# CF_FMC_DE.net
KiCad netlist of a schematic drawn in Altium Designer
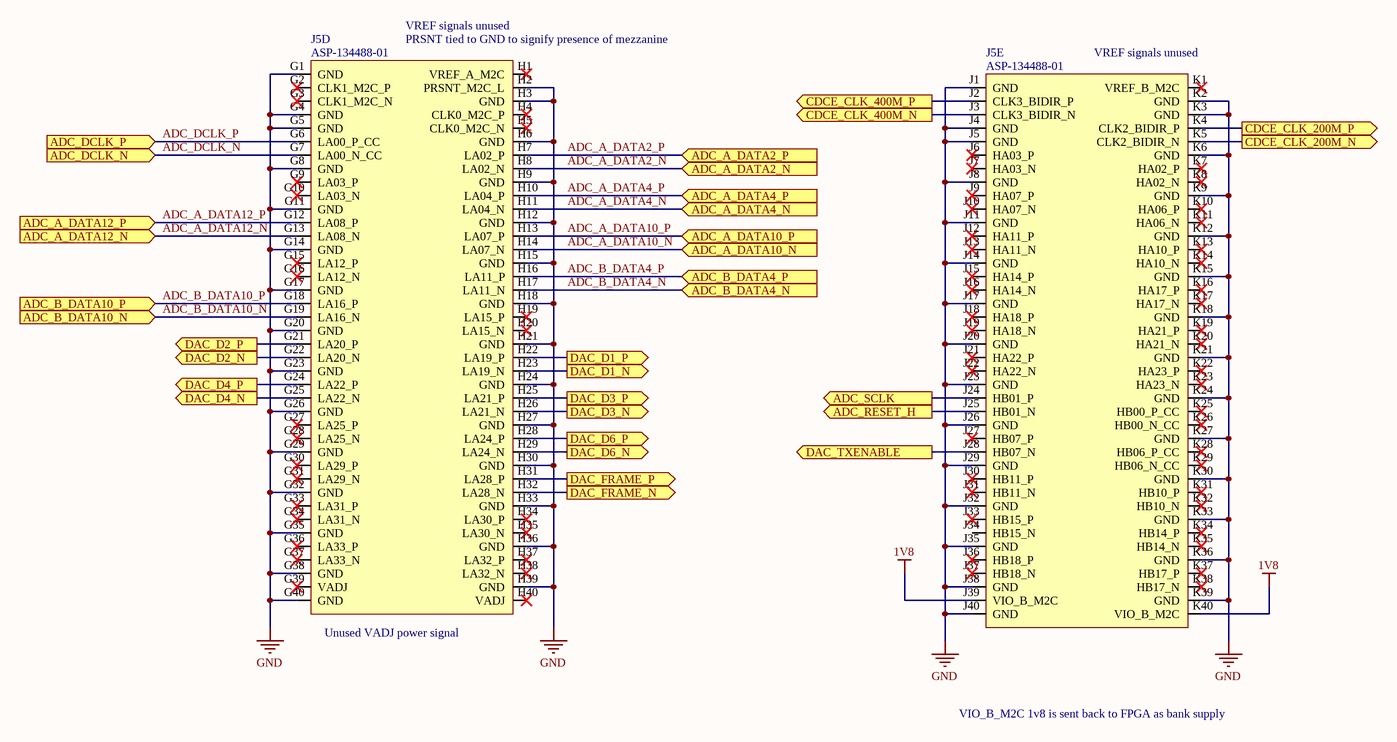
[diagram p0: CF_FMC_DE.SchDoc]

(export (version "E")
  (design (tool "Eeschema 10.0.6"))
  (components
    (comp (ref "J5")
      (value "ASP-134488-01")
      (footprint "CONN_SAMTEC_ASP-134488-01")
      (description "CONN - VITA 57 MEZZ MALE (DAUGHTERBOARD) HIGH DENSITY - SMD-400")
      (fields
        (field (name "VOLTAGE") "240VAC")
        (field (name "MFG") "Samtec")
        (field (name "CREATEDBY") "Jonathan Bouchard")
      )
      (libsource (lib "S7CAS_Lib2019_REV1_00") (part "CONN_SAMTEC_ASP-134488-01"))
    )
  )
  (nets
    (net (code "1") (name "/ADC_A_DATA2_N") (class "Default")
      (node (ref "J5") (pin "H8") (pinfunction "LA02_N_H8") (pintype "passive"))
    )
    (net (code "2") (name "/ADC_A_DATA2_P") (class "Default")
      (node (ref "J5") (pin "H7") (pinfunction "LA02_P_H7") (pintype "passive"))
    )
    (net (code "3") (name "/ADC_A_DATA4_N") (class "Default")
      (node (ref "J5") (pin "H11") (pinfunction "LA04_N_H11") (pintype "passive"))
    )
    (net (code "4") (name "/ADC_A_DATA4_P") (class "Default")
      (node (ref "J5") (pin "H10") (pinfunction "LA04_P_H10") (pintype "passive"))
    )
    (net (code "5") (name "/ADC_A_DATA10_N") (class "Default")
      (node (ref "J5") (pin "H14") (pinfunction "LA07_N_H14") (pintype "passive"))
    )
    (net (code "6") (name "/ADC_A_DATA10_P") (class "Default")
      (node (ref "J5") (pin "H13") (pinfunction "LA07_P_H13") (pintype "passive"))
    )
    (net (code "7") (name "/ADC_A_DATA12_N") (class "Default")
      (node (ref "J5") (pin "G13") (pinfunction "LA08_N_G13") (pintype "passive"))
    )
    (net (code "8") (name "/ADC_A_DATA12_P") (class "Default")
      (node (ref "J5") (pin "G12") (pinfunction "LA08_P_G12") (pintype "passive"))
    )
    (net (code "9") (name "/ADC_B_DATA4_N") (class "Default")
      (node (ref "J5") (pin "H17") (pinfunction "LA11_N_H17") (pintype "passive"))
    )
    (net (code "10") (name "/ADC_B_DATA4_P") (class "Default")
      (node (ref "J5") (pin "H16") (pinfunction "LA11_P_H16") (pintype "passive"))
    )
    (net (code "11") (name "/ADC_B_DATA10_N") (class "Default")
      (node (ref "J5") (pin "G19") (pinfunction "LA16_N_G19") (pintype "passive"))
    )
    (net (code "12") (name "/ADC_B_DATA10_P") (class "Default")
      (node (ref "J5") (pin "G18") (pinfunction "LA16_P_G18") (pintype "passive"))
    )
    (net (code "13") (name "/ADC_DCLK_N") (class "Default")
      (node (ref "J5") (pin "G7") (pinfunction "LA00_N_CC_G7") (pintype "passive"))
    )
    (net (code "14") (name "/ADC_DCLK_P") (class "Default")
      (node (ref "J5") (pin "G6") (pinfunction "LA00_P_CC_G6") (pintype "passive"))
    )
    (net (code "15") (name "/ADC_RESET_H") (class "Default")
      (node (ref "J5") (pin "J25") (pinfunction "HB01_N_J25") (pintype "passive"))
    )
    (net (code "16") (name "/ADC_SCLK") (class "Default")
      (node (ref "J5") (pin "J24") (pinfunction "HB01_P_J24") (pintype "passive"))
    )
    (net (code "17") (name "/CDCE_CLK_200M_N") (class "Default")
      (node (ref "J5") (pin "K5") (pinfunction "CLK2_BIDIR_N_K5") (pintype "passive"))
    )
    (net (code "18") (name "/CDCE_CLK_200M_P") (class "Default")
      (node (ref "J5") (pin "K4") (pinfunction "CLK2_BIDIR_P_K4") (pintype "passive"))
    )
    (net (code "19") (name "/CDCE_CLK_400M_N") (class "Default")
      (node (ref "J5") (pin "J3") (pinfunction "CLK3_BIDIR_N_J3") (pintype "passive"))
    )
    (net (code "20") (name "/CDCE_CLK_400M_P") (class "Default")
      (node (ref "J5") (pin "J2") (pinfunction "CLK3_BIDIR_P_J2") (pintype "passive"))
    )
    (net (code "21") (name "/DAC_D1_N") (class "Default")
      (node (ref "J5") (pin "H23") (pinfunction "LA19_N_H23") (pintype "passive"))
    )
    (net (code "22") (name "/DAC_D1_P") (class "Default")
      (node (ref "J5") (pin "H22") (pinfunction "LA19_P_H22") (pintype "passive"))
    )
    (net (code "23") (name "/DAC_D2_N") (class "Default")
      (node (ref "J5") (pin "G22") (pinfunction "LA20_N_G22") (pintype "passive"))
    )
    (net (code "24") (name "/DAC_D2_P") (class "Default")
      (node (ref "J5") (pin "G21") (pinfunction "LA20_P_G21") (pintype "passive"))
    )
    (net (code "25") (name "/DAC_D3_N") (class "Default")
      (node (ref "J5") (pin "H26") (pinfunction "LA21_N_H26") (pintype "passive"))
    )
    (net (code "26") (name "/DAC_D3_P") (class "Default")
      (node (ref "J5") (pin "H25") (pinfunction "LA21_P_H25") (pintype "passive"))
    )
    (net (code "27") (name "/DAC_D4_N") (class "Default")
      (node (ref "J5") (pin "G25") (pinfunction "LA22_N_G25") (pintype "passive"))
    )
    (net (code "28") (name "/DAC_D4_P") (class "Default")
      (node (ref "J5") (pin "G24") (pinfunction "LA22_P_G24") (pintype "passive"))
    )
    (net (code "29") (name "/DAC_D6_N") (class "Default")
      (node (ref "J5") (pin "H29") (pinfunction "LA24_N_H29") (pintype "passive"))
    )
    (net (code "30") (name "/DAC_D6_P") (class "Default")
      (node (ref "J5") (pin "H28") (pinfunction "LA24_P_H28") (pintype "passive"))
    )
    (net (code "31") (name "/DAC_FRAME_N") (class "Default")
      (node (ref "J5") (pin "H32") (pinfunction "LA28_N_H32") (pintype "passive"))
    )
    (net (code "32") (name "/DAC_FRAME_P") (class "Default")
      (node (ref "J5") (pin "H31") (pinfunction "LA28_P_H31") (pintype "passive"))
    )
    (net (code "33") (name "/DAC_TXENABLE") (class "Default")
      (node (ref "J5") (pin "J28") (pinfunction "HB07_N_J28") (pintype "passive"))
    )
    (net (code "34") (name "1V8") (class "Default")
      (node (ref "J5") (pin "J39") (pinfunction "VIO_B_M2C_J39") (pintype "passive"))
      (node (ref "J5") (pin "K40") (pinfunction "VIO_B_M2C_K40") (pintype "passive"))
    )
    (net (code "35") (name "GND") (class "Default")
      (node (ref "J5") (pin "G1") (pinfunction "GND_G1") (pintype "passive"))
      (node (ref "J5") (pin "G11") (pinfunction "GND_G11") (pintype "passive"))
      (node (ref "J5") (pin "G14") (pinfunction "GND_G14") (pintype "passive"))
      (node (ref "J5") (pin "G17") (pinfunction "GND_G17") (pintype "passive"))
      (node (ref "J5") (pin "G20") (pinfunction "GND_G20") (pintype "passive"))
      (node (ref "J5") (pin "G23") (pinfunction "GND_G23") (pintype "passive"))
      (node (ref "J5") (pin "G26") (pinfunction "GND_G26") (pintype "passive"))
      (node (ref "J5") (pin "G29") (pinfunction "GND_G29") (pintype "passive"))
      (node (ref "J5") (pin "G32") (pinfunction "GND_G32") (pintype "passive"))
      (node (ref "J5") (pin "G35") (pinfunction "GND_G35") (pintype "passive"))
      (node (ref "J5") (pin "G38") (pinfunction "GND_G38") (pintype "passive"))
      (node (ref "J5") (pin "G4") (pinfunction "GND_G4") (pintype "passive"))
      (node (ref "J5") (pin "G40") (pinfunction "GND_G40") (pintype "passive"))
      (node (ref "J5") (pin "G5") (pinfunction "GND_G5") (pintype "passive"))
      (node (ref "J5") (pin "G8") (pinfunction "GND_G8") (pintype "passive"))
      (node (ref "J5") (pin "H12") (pinfunction "GND_H12") (pintype "passive"))
      (node (ref "J5") (pin "H15") (pinfunction "GND_H15") (pintype "passive"))
      (node (ref "J5") (pin "H18") (pinfunction "GND_H18") (pintype "passive"))
      (node (ref "J5") (pin "H2") (pinfunction "PRSNT_M2C_L_H2") (pintype "passive"))
      (node (ref "J5") (pin "H21") (pinfunction "GND_H21") (pintype "passive"))
      (node (ref "J5") (pin "H24") (pinfunction "GND_H24") (pintype "passive"))
      (node (ref "J5") (pin "H27") (pinfunction "GND_H27") (pintype "passive"))
      (node (ref "J5") (pin "H3") (pinfunction "GND_H3") (pintype "passive"))
      (node (ref "J5") (pin "H30") (pinfunction "GND_H30") (pintype "passive"))
      (node (ref "J5") (pin "H33") (pinfunction "GND_H33") (pintype "passive"))
      (node (ref "J5") (pin "H36") (pinfunction "GND_H36") (pintype "passive"))
      (node (ref "J5") (pin "H39") (pinfunction "GND_H39") (pintype "passive"))
      (node (ref "J5") (pin "H6") (pinfunction "GND_H6") (pintype "passive"))
      (node (ref "J5") (pin "H9") (pinfunction "GND_H9") (pintype "passive"))
      (node (ref "J5") (pin "J1") (pinfunction "GND_J1") (pintype "passive"))
      (node (ref "J5") (pin "J11") (pinfunction "GND_J11") (pintype "passive"))
      (node (ref "J5") (pin "J14") (pinfunction "GND_J14") (pintype "passive"))
      (node (ref "J5") (pin "J17") (pinfunction "GND_J17") (pintype "passive"))
      (node (ref "J5") (pin "J20") (pinfunction "GND_J20") (pintype "passive"))
      (node (ref "J5") (pin "J23") (pinfunction "GND_J23") (pintype "passive"))
      (node (ref "J5") (pin "J26") (pinfunction "GND_J26") (pintype "passive"))
      (node (ref "J5") (pin "J29") (pinfunction "GND_J29") (pintype "passive"))
      (node (ref "J5") (pin "J32") (pinfunction "GND_J32") (pintype "passive"))
      (node (ref "J5") (pin "J35") (pinfunction "GND_J35") (pintype "passive"))
      (node (ref "J5") (pin "J38") (pinfunction "GND_J38") (pintype "passive"))
      (node (ref "J5") (pin "J4") (pinfunction "GND_J4") (pintype "passive"))
      (node (ref "J5") (pin "J40") (pinfunction "GND_J40") (pintype "passive"))
      (node (ref "J5") (pin "J5") (pinfunction "GND_J5") (pintype "passive"))
      (node (ref "J5") (pin "J8") (pinfunction "GND_J8") (pintype "passive"))
      (node (ref "J5") (pin "K12") (pinfunction "GND_K12") (pintype "passive"))
      (node (ref "J5") (pin "K15") (pinfunction "GND_K15") (pintype "passive"))
      (node (ref "J5") (pin "K18") (pinfunction "GND_K18") (pintype "passive"))
      (node (ref "J5") (pin "K2") (pinfunction "GND_K2") (pintype "passive"))
      (node (ref "J5") (pin "K21") (pinfunction "GND_K21") (pintype "passive"))
      (node (ref "J5") (pin "K24") (pinfunction "GND_K24") (pintype "passive"))
      (node (ref "J5") (pin "K27") (pinfunction "GND_K27") (pintype "passive"))
      (node (ref "J5") (pin "K3") (pinfunction "GND_K3") (pintype "passive"))
      (node (ref "J5") (pin "K30") (pinfunction "GND_K30") (pintype "passive"))
      (node (ref "J5") (pin "K33") (pinfunction "GND_K33") (pintype "passive"))
      (node (ref "J5") (pin "K36") (pinfunction "GND_K36") (pintype "passive"))
      (node (ref "J5") (pin "K39") (pinfunction "GND_K39") (pintype "passive"))
      (node (ref "J5") (pin "K6") (pinfunction "GND_K6") (pintype "passive"))
      (node (ref "J5") (pin "K9") (pinfunction "GND_K9") (pintype "passive"))
    )
    (net (code "36") (name "unconnected-(J5D-CLK0_M2C_N-PadH5)") (class "Default")
      (node (ref "J5") (pin "H5") (pinfunction "CLK0_M2C_N_H5") (pintype "passive+no_connect"))
    )
    (net (code "37") (name "unconnected-(J5D-CLK0_M2C_P-PadH4)") (class "Default")
      (node (ref "J5") (pin "H4") (pinfunction "CLK0_M2C_P_H4") (pintype "passive+no_connect"))
    )
    (net (code "38") (name "unconnected-(J5D-CLK1_M2C_N-PadG3)") (class "Default")
      (node (ref "J5") (pin "G3") (pinfunction "CLK1_M2C_N_G3") (pintype "passive+no_connect"))
    )
    (net (code "39") (name "unconnected-(J5D-CLK1_M2C_P-PadG2)") (class "Default")
      (node (ref "J5") (pin "G2") (pinfunction "CLK1_M2C_P_G2") (pintype "passive+no_connect"))
    )
    (net (code "40") (name "unconnected-(J5D-LA03_N-PadG10)") (class "Default")
      (node (ref "J5") (pin "G10") (pinfunction "LA03_N_G10") (pintype "passive+no_connect"))
    )
    (net (code "41") (name "unconnected-(J5D-LA03_P-PadG9)") (class "Default")
      (node (ref "J5") (pin "G9") (pinfunction "LA03_P_G9") (pintype "passive+no_connect"))
    )
    (net (code "42") (name "unconnected-(J5D-LA12_N-PadG16)") (class "Default")
      (node (ref "J5") (pin "G16") (pinfunction "LA12_N_G16") (pintype "passive+no_connect"))
    )
    (net (code "43") (name "unconnected-(J5D-LA12_P-PadG15)") (class "Default")
      (node (ref "J5") (pin "G15") (pinfunction "LA12_P_G15") (pintype "passive+no_connect"))
    )
    (net (code "44") (name "unconnected-(J5D-LA15_N-PadH20)") (class "Default")
      (node (ref "J5") (pin "H20") (pinfunction "LA15_N_H20") (pintype "passive+no_connect"))
    )
    (net (code "45") (name "unconnected-(J5D-LA15_P-PadH19)") (class "Default")
      (node (ref "J5") (pin "H19") (pinfunction "LA15_P_H19") (pintype "passive+no_connect"))
    )
    (net (code "46") (name "unconnected-(J5D-LA25_N-PadG28)") (class "Default")
      (node (ref "J5") (pin "G28") (pinfunction "LA25_N_G28") (pintype "passive+no_connect"))
    )
    (net (code "47") (name "unconnected-(J5D-LA25_P-PadG27)") (class "Default")
      (node (ref "J5") (pin "G27") (pinfunction "LA25_P_G27") (pintype "passive+no_connect"))
    )
    (net (code "48") (name "unconnected-(J5D-LA29_N-PadG31)") (class "Default")
      (node (ref "J5") (pin "G31") (pinfunction "LA29_N_G31") (pintype "passive+no_connect"))
    )
    (net (code "49") (name "unconnected-(J5D-LA29_P-PadG30)") (class "Default")
      (node (ref "J5") (pin "G30") (pinfunction "LA29_P_G30") (pintype "passive+no_connect"))
    )
    (net (code "50") (name "unconnected-(J5D-LA30_N-PadH35)") (class "Default")
      (node (ref "J5") (pin "H35") (pinfunction "LA30_N_H35") (pintype "passive+no_connect"))
    )
    (net (code "51") (name "unconnected-(J5D-LA30_P-PadH34)") (class "Default")
      (node (ref "J5") (pin "H34") (pinfunction "LA30_P_H34") (pintype "passive+no_connect"))
    )
    (net (code "52") (name "unconnected-(J5D-LA31_N-PadG34)") (class "Default")
      (node (ref "J5") (pin "G34") (pinfunction "LA31_N_G34") (pintype "passive+no_connect"))
    )
    (net (code "53") (name "unconnected-(J5D-LA31_P-PadG33)") (class "Default")
      (node (ref "J5") (pin "G33") (pinfunction "LA31_P_G33") (pintype "passive+no_connect"))
    )
    (net (code "54") (name "unconnected-(J5D-LA32_N-PadH38)") (class "Default")
      (node (ref "J5") (pin "H38") (pinfunction "LA32_N_H38") (pintype "passive+no_connect"))
    )
    (net (code "55") (name "unconnected-(J5D-LA32_P-PadH37)") (class "Default")
      (node (ref "J5") (pin "H37") (pinfunction "LA32_P_H37") (pintype "passive+no_connect"))
    )
    (net (code "56") (name "unconnected-(J5D-LA33_N-PadG37)") (class "Default")
      (node (ref "J5") (pin "G37") (pinfunction "LA33_N_G37") (pintype "passive+no_connect"))
    )
    (net (code "57") (name "unconnected-(J5D-LA33_P-PadG36)") (class "Default")
      (node (ref "J5") (pin "G36") (pinfunction "LA33_P_G36") (pintype "passive+no_connect"))
    )
    (net (code "58") (name "unconnected-(J5D-VADJ-PadG39)") (class "Default")
      (node (ref "J5") (pin "G39") (pinfunction "VADJ_G39") (pintype "passive+no_connect"))
    )
    (net (code "59") (name "unconnected-(J5D-VADJ-PadH40)") (class "Default")
      (node (ref "J5") (pin "H40") (pinfunction "VADJ_H40") (pintype "passive+no_connect"))
    )
    (net (code "60") (name "unconnected-(J5D-VREF_A_M2C-PadH1)") (class "Default")
      (node (ref "J5") (pin "H1") (pinfunction "VREF_A_M2C_H1") (pintype "passive+no_connect"))
    )
    (net (code "61") (name "unconnected-(J5E-HA02_N-PadK8)") (class "Default")
      (node (ref "J5") (pin "K8") (pinfunction "HA02_N_K8") (pintype "passive+no_connect"))
    )
    (net (code "62") (name "unconnected-(J5E-HA02_P-PadK7)") (class "Default")
      (node (ref "J5") (pin "K7") (pinfunction "HA02_P_K7") (pintype "passive+no_connect"))
    )
    (net (code "63") (name "unconnected-(J5E-HA03_N-PadJ7)") (class "Default")
      (node (ref "J5") (pin "J7") (pinfunction "HA03_N_J7") (pintype "passive+no_connect"))
    )
    (net (code "64") (name "unconnected-(J5E-HA03_P-PadJ6)") (class "Default")
      (node (ref "J5") (pin "J6") (pinfunction "HA03_P_J6") (pintype "passive+no_connect"))
    )
    (net (code "65") (name "unconnected-(J5E-HA06_N-PadK11)") (class "Default")
      (node (ref "J5") (pin "K11") (pinfunction "HA06_N_K11") (pintype "passive+no_connect"))
    )
    (net (code "66") (name "unconnected-(J5E-HA06_P-PadK10)") (class "Default")
      (node (ref "J5") (pin "K10") (pinfunction "HA06_P_K10") (pintype "passive+no_connect"))
    )
    (net (code "67") (name "unconnected-(J5E-HA07_N-PadJ10)") (class "Default")
      (node (ref "J5") (pin "J10") (pinfunction "HA07_N_J10") (pintype "passive+no_connect"))
    )
    (net (code "68") (name "unconnected-(J5E-HA07_P-PadJ9)") (class "Default")
      (node (ref "J5") (pin "J9") (pinfunction "HA07_P_J9") (pintype "passive+no_connect"))
    )
    (net (code "69") (name "unconnected-(J5E-HA10_N-PadK14)") (class "Default")
      (node (ref "J5") (pin "K14") (pinfunction "HA10_N_K14") (pintype "passive+no_connect"))
    )
    (net (code "70") (name "unconnected-(J5E-HA10_P-PadK13)") (class "Default")
      (node (ref "J5") (pin "K13") (pinfunction "HA10_P_K13") (pintype "passive+no_connect"))
    )
    (net (code "71") (name "unconnected-(J5E-HA11_N-PadJ13)") (class "Default")
      (node (ref "J5") (pin "J13") (pinfunction "HA11_N_J13") (pintype "passive+no_connect"))
    )
    (net (code "72") (name "unconnected-(J5E-HA11_P-PadJ12)") (class "Default")
      (node (ref "J5") (pin "J12") (pinfunction "HA11_P_J12") (pintype "passive+no_connect"))
    )
    (net (code "73") (name "unconnected-(J5E-HA14_N-PadJ16)") (class "Default")
      (node (ref "J5") (pin "J16") (pinfunction "HA14_N_J16") (pintype "passive+no_connect"))
    )
    (net (code "74") (name "unconnected-(J5E-HA14_P-PadJ15)") (class "Default")
      (node (ref "J5") (pin "J15") (pinfunction "HA14_P_J15") (pintype "passive+no_connect"))
    )
    (net (code "75") (name "unconnected-(J5E-HA17_N-PadK17)") (class "Default")
      (node (ref "J5") (pin "K17") (pinfunction "HA17_N_K17") (pintype "passive+no_connect"))
    )
    (net (code "76") (name "unconnected-(J5E-HA17_P-PadK16)") (class "Default")
      (node (ref "J5") (pin "K16") (pinfunction "HA17_P_K16") (pintype "passive+no_connect"))
    )
    (net (code "77") (name "unconnected-(J5E-HA18_N-PadJ19)") (class "Default")
      (node (ref "J5") (pin "J19") (pinfunction "HA18_N_J19") (pintype "passive+no_connect"))
    )
    (net (code "78") (name "unconnected-(J5E-HA18_P-PadJ18)") (class "Default")
      (node (ref "J5") (pin "J18") (pinfunction "HA18_P_J18") (pintype "passive+no_connect"))
    )
    (net (code "79") (name "unconnected-(J5E-HA21_N-PadK20)") (class "Default")
      (node (ref "J5") (pin "K20") (pinfunction "HA21_N_K20") (pintype "passive+no_connect"))
    )
    (net (code "80") (name "unconnected-(J5E-HA21_P-PadK19)") (class "Default")
      (node (ref "J5") (pin "K19") (pinfunction "HA21_P_K19") (pintype "passive+no_connect"))
    )
    (net (code "81") (name "unconnected-(J5E-HA22_N-PadJ22)") (class "Default")
      (node (ref "J5") (pin "J22") (pinfunction "HA22_N_J22") (pintype "passive+no_connect"))
    )
    (net (code "82") (name "unconnected-(J5E-HA22_P-PadJ21)") (class "Default")
      (node (ref "J5") (pin "J21") (pinfunction "HA22_P_J21") (pintype "passive+no_connect"))
    )
    (net (code "83") (name "unconnected-(J5E-HA23_N-PadK23)") (class "Default")
      (node (ref "J5") (pin "K23") (pinfunction "HA23_N_K23") (pintype "passive+no_connect"))
    )
    (net (code "84") (name "unconnected-(J5E-HA23_P-PadK22)") (class "Default")
      (node (ref "J5") (pin "K22") (pinfunction "HA23_P_K22") (pintype "passive+no_connect"))
    )
    (net (code "85") (name "unconnected-(J5E-HB00_N_CC-PadK26)") (class "Default")
      (node (ref "J5") (pin "K26") (pinfunction "HB00_N_CC_K26") (pintype "passive+no_connect"))
    )
    (net (code "86") (name "unconnected-(J5E-HB00_P_CC-PadK25)") (class "Default")
      (node (ref "J5") (pin "K25") (pinfunction "HB00_P_CC_K25") (pintype "passive+no_connect"))
    )
    (net (code "87") (name "unconnected-(J5E-HB06_N_CC-PadK29)") (class "Default")
      (node (ref "J5") (pin "K29") (pinfunction "HB06_N_CC_K29") (pintype "passive+no_connect"))
    )
    (net (code "88") (name "unconnected-(J5E-HB06_P_CC-PadK28)") (class "Default")
      (node (ref "J5") (pin "K28") (pinfunction "HB06_P_CC_K28") (pintype "passive+no_connect"))
    )
    (net (code "89") (name "unconnected-(J5E-HB07_P-PadJ27)") (class "Default")
      (node (ref "J5") (pin "J27") (pinfunction "HB07_P_J27") (pintype "passive+no_connect"))
    )
    (net (code "90") (name "unconnected-(J5E-HB10_N-PadK32)") (class "Default")
      (node (ref "J5") (pin "K32") (pinfunction "HB10_N_K32") (pintype "passive+no_connect"))
    )
    (net (code "91") (name "unconnected-(J5E-HB10_P-PadK31)") (class "Default")
      (node (ref "J5") (pin "K31") (pinfunction "HB10_P_K31") (pintype "passive+no_connect"))
    )
    (net (code "92") (name "unconnected-(J5E-HB11_N-PadJ31)") (class "Default")
      (node (ref "J5") (pin "J31") (pinfunction "HB11_N_J31") (pintype "passive+no_connect"))
    )
    (net (code "93") (name "unconnected-(J5E-HB11_P-PadJ30)") (class "Default")
      (node (ref "J5") (pin "J30") (pinfunction "HB11_P_J30") (pintype "passive+no_connect"))
    )
    (net (code "94") (name "unconnected-(J5E-HB14_N-PadK35)") (class "Default")
      (node (ref "J5") (pin "K35") (pinfunction "HB14_N_K35") (pintype "passive+no_connect"))
    )
    (net (code "95") (name "unconnected-(J5E-HB14_P-PadK34)") (class "Default")
      (node (ref "J5") (pin "K34") (pinfunction "HB14_P_K34") (pintype "passive+no_connect"))
    )
    (net (code "96") (name "unconnected-(J5E-HB15_N-PadJ34)") (class "Default")
      (node (ref "J5") (pin "J34") (pinfunction "HB15_N_J34") (pintype "passive"))
    )
    (net (code "97") (name "unconnected-(J5E-HB15_P-PadJ33)") (class "Default")
      (node (ref "J5") (pin "J33") (pinfunction "HB15_P_J33") (pintype "passive+no_connect"))
    )
    (net (code "98") (name "unconnected-(J5E-HB17_N-PadK38)") (class "Default")
      (node (ref "J5") (pin "K38") (pinfunction "HB17_N_K38") (pintype "passive+no_connect"))
    )
    (net (code "99") (name "unconnected-(J5E-HB17_P-PadK37)") (class "Default")
      (node (ref "J5") (pin "K37") (pinfunction "HB17_P_K37") (pintype "passive+no_connect"))
    )
    (net (code "100") (name "unconnected-(J5E-HB18_N-PadJ37)") (class "Default")
      (node (ref "J5") (pin "J37") (pinfunction "HB18_N_J37") (pintype "passive+no_connect"))
    )
    (net (code "101") (name "unconnected-(J5E-HB18_P-PadJ36)") (class "Default")
      (node (ref "J5") (pin "J36") (pinfunction "HB18_P_J36") (pintype "passive+no_connect"))
    )
    (net (code "102") (name "unconnected-(J5E-VREF_B_M2C-PadK1)") (class "Default")
      (node (ref "J5") (pin "K1") (pinfunction "VREF_B_M2C_K1") (pintype "passive+no_connect"))
    )
  )
)
